# GWLSensorv3.net
KiCad netlist of a schematic drawn in EAGLE
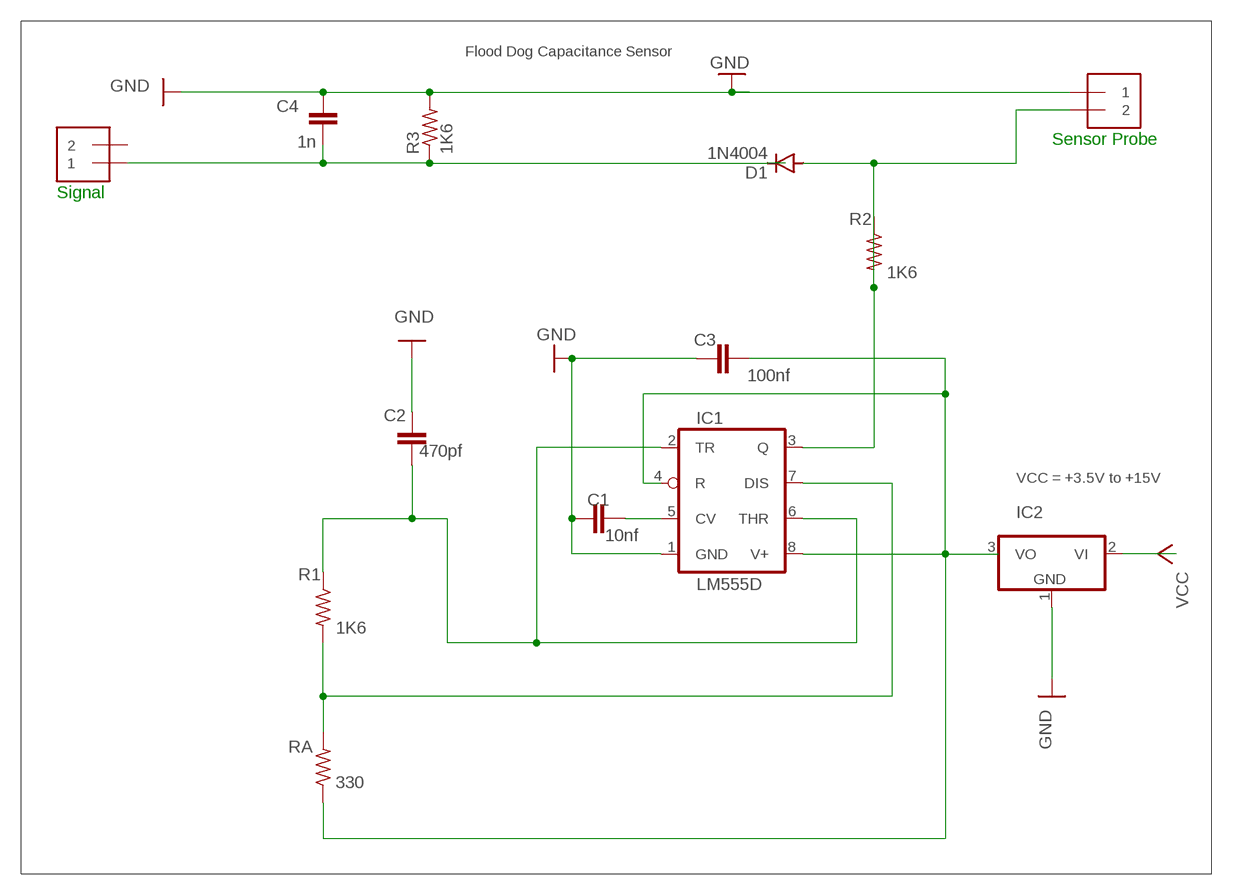
[diagram p0: schematic, sheet 1]

(export (version "E")
  (design (tool "Eeschema 10.0.6"))
  (components
    (comp (ref "C1")
      (value "10nf")
      (footprint "eagle-import:C0805")
      (libsource (lib "eagle-import") (part "C-EUC0805"))
    )
    (comp (ref "C2")
      (value "470pf")
      (footprint "eagle-import:C0805")
      (libsource (lib "eagle-import") (part "C-EUC0805"))
    )
    (comp (ref "C3")
      (value "100nf")
      (footprint "eagle-import:C0805")
      (libsource (lib "eagle-import") (part "C-EUC0805"))
    )
    (comp (ref "C4")
      (value "1n")
      (footprint "eagle-import:C0805")
      (libsource (lib "eagle-import") (part "C-EUC0805"))
    )
    (comp (ref "D1")
      (value "1N4004")
      (footprint "eagle-import:DO41-10")
      (libsource (lib "eagle-import") (part "1N4004"))
    )
    (comp (ref "IC1")
      (value "LM555D")
      (footprint "eagle-import:SO08")
      (libsource (lib "eagle-import") (part "555DLM"))
    )
    (comp (ref "IC2")
      (value "79L15Z")
      (footprint "eagle-import:TO92")
      (libsource (lib "eagle-import") (part "79ZL15"))
    )
    (comp (ref "PROBE")
      (value "1X2-3.5MM")
      (footprint "eagle-import:1X2-3.5MM")
      (libsource (lib "eagle-import") (part "1X2-3.5MM"))
    )
    (comp (ref "R1")
      (value "1K6")
      (footprint "eagle-import:R0805")
      (libsource (lib "eagle-import") (part "R-US_R0805"))
    )
    (comp (ref "R2")
      (value "1K6")
      (footprint "eagle-import:R0805")
      (libsource (lib "eagle-import") (part "R-US_R0805"))
    )
    (comp (ref "R3")
      (value "1K6")
      (footprint "eagle-import:R0805")
      (libsource (lib "eagle-import") (part "R-US_R0805"))
    )
    (comp (ref "RA")
      (value "330")
      (footprint "eagle-import:R0805")
      (libsource (lib "eagle-import") (part "R-US_R0805"))
    )
    (comp (ref "SIGNAL")
      (value "1X2-3.5MM")
      (footprint "eagle-import:1X2-3.5MM")
      (libsource (lib "eagle-import") (part "1X2-3.5MM"))
    )
  )
  (nets
    (net (code "1") (name "GND") (class "Default")
      (node (ref "C1") (pin "1") (pinfunction "1_1") (pintype "passive"))
      (node (ref "C2") (pin "1") (pinfunction "1_1") (pintype "passive"))
      (node (ref "C3") (pin "1") (pinfunction "1_1") (pintype "passive"))
      (node (ref "C4") (pin "2") (pinfunction "2_2") (pintype "passive"))
      (node (ref "IC1") (pin "1") (pinfunction "GND_1") (pintype "power_in"))
      (node (ref "IC2") (pin "1") (pinfunction "GND_1") (pintype "passive"))
      (node (ref "PROBE") (pin "1") (pinfunction "1_1") (pintype "passive"))
      (node (ref "R3") (pin "2") (pinfunction "2_2") (pintype "passive"))
    )
    (net (code "2") (name "Net-(C4-Pad1)") (class "Default")
      (node (ref "C4") (pin "1") (pinfunction "1_1") (pintype "passive"))
      (node (ref "D1") (pin "C") (pinfunction "C_C") (pintype "passive"))
      (node (ref "R3") (pin "1") (pinfunction "1_1") (pintype "passive"))
      (node (ref "SIGNAL") (pin "1") (pinfunction "1_1") (pintype "passive"))
    )
    (net (code "3") (name "Net-(IC1-CV)") (class "Default")
      (node (ref "C1") (pin "2") (pinfunction "2_2") (pintype "passive"))
      (node (ref "IC1") (pin "5") (pinfunction "CV_5") (pintype "input"))
    )
    (net (code "4") (name "Net-(IC1-DIS)") (class "Default")
      (node (ref "IC1") (pin "7") (pinfunction "DIS_7") (pintype "input"))
      (node (ref "R1") (pin "2") (pinfunction "2_2") (pintype "passive"))
      (node (ref "RA") (pin "2") (pinfunction "2_2") (pintype "passive"))
    )
    (net (code "5") (name "Net-(IC1-Q)") (class "Default")
      (node (ref "D1") (pin "A") (pinfunction "A_A") (pintype "passive"))
      (node (ref "IC1") (pin "3") (pinfunction "Q_3") (pintype "output"))
      (node (ref "PROBE") (pin "2") (pinfunction "2_2") (pintype "passive"))
      (node (ref "R2") (pin "1") (pinfunction "1_1") (pintype "passive"))
      (node (ref "R2") (pin "2") (pinfunction "2_2") (pintype "passive"))
    )
    (net (code "6") (name "Net-(IC1-R)") (class "Default")
      (node (ref "C3") (pin "2") (pinfunction "2_2") (pintype "passive"))
      (node (ref "IC1") (pin "4") (pinfunction "R_4") (pintype "input"))
      (node (ref "IC1") (pin "8") (pinfunction "V+_8") (pintype "power_in"))
      (node (ref "IC2") (pin "3") (pinfunction "VO_3") (pintype "passive"))
      (node (ref "RA") (pin "1") (pinfunction "1_1") (pintype "passive"))
    )
    (net (code "7") (name "Net-(IC1-THR)") (class "Default")
      (node (ref "C2") (pin "2") (pinfunction "2_2") (pintype "passive"))
      (node (ref "IC1") (pin "2") (pinfunction "TR_2") (pintype "input"))
      (node (ref "IC1") (pin "6") (pinfunction "THR_6") (pintype "input"))
      (node (ref "R1") (pin "1") (pinfunction "1_1") (pintype "passive"))
    )
    (net (code "8") (name "VCC") (class "Default")
      (node (ref "IC2") (pin "2") (pinfunction "VI_2") (pintype "input"))
    )
    (net (code "9") (name "unconnected-(SIGNAL-Pad2)") (class "Default")
      (node (ref "SIGNAL") (pin "2") (pinfunction "2_2") (pintype "passive"))
    )
  )
)
